# Button_ClockLed.net
KiCad netlist of a schematic drawn in Altium Designer
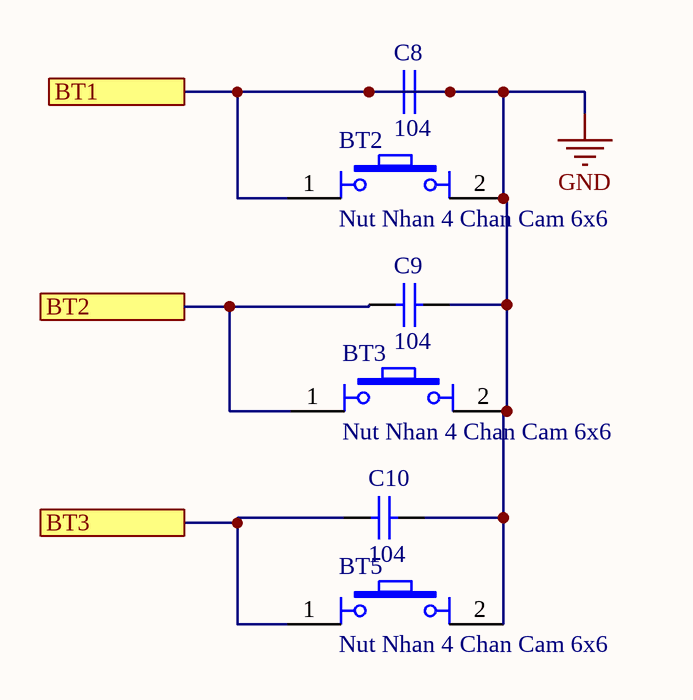
[diagram p0: Button_ClockLed.SchDoc]

(export (version "E")
  (design (tool "Eeschema 10.0.6"))
  (components
    (comp (ref "BT2")
      (value "Nut Nhan 4 Chan Cam 6x6")
      (footprint "Nut Nhan 4 Chan Cam 6x6")
      (description "Nut Nhan 4 Chan 6x6mm")
      (libsource (lib "Altium_Lib_by_KhueNguyenCreator") (part "Nut Nhan 4 Chan Cam 6x6"))
    )
    (comp (ref "BT3")
      (value "Nut Nhan 4 Chan Cam 6x6")
      (footprint "Nut Nhan 4 Chan Cam 6x6")
      (description "Nut Nhan 4 Chan 6x6mm")
      (libsource (lib "Altium_Lib_by_KhueNguyenCreator") (part "Nut Nhan 4 Chan Cam 6x6"))
    )
    (comp (ref "BT5")
      (value "Nut Nhan 4 Chan Cam 6x6")
      (footprint "Nut Nhan 4 Chan Cam 6x6")
      (description "Nut Nhan 4 Chan 6x6mm")
      (libsource (lib "Altium_Lib_by_KhueNguyenCreator") (part "Nut Nhan 4 Chan Cam 6x6"))
    )
    (comp (ref "C8")
      (value "104")
      (footprint "tu 0805")
      (description "Dán")
      (libsource (lib "Altium_Lib_by_KhueNguyenCreator") (part "Tu 0805 104 50V 10%"))
    )
    (comp (ref "C9")
      (value "104")
      (footprint "tu 0805")
      (description "Dán")
      (libsource (lib "Altium_Lib_by_KhueNguyenCreator") (part "Tu 0805 104 50V 10%"))
    )
    (comp (ref "C10")
      (value "104")
      (footprint "tu 0805")
      (description "Dán")
      (libsource (lib "Altium_Lib_by_KhueNguyenCreator") (part "Tu 0805 104 50V 10%"))
    )
  )
  (nets
    (net (code "1") (name "/BT2") (class "Default")
      (node (ref "BT3") (pin "1") (pintype "passive"))
      (node (ref "C9") (pin "1") (pinfunction "1_1") (pintype "passive"))
    )
    (net (code "2") (name "/BT3") (class "Default")
      (node (ref "BT5") (pin "1") (pintype "passive"))
      (node (ref "C10") (pin "2") (pinfunction "2_2") (pintype "passive"))
    )
    (net (code "3") (name "GND") (class "Default")
      (node (ref "BT2") (pin "1") (pintype "passive"))
      (node (ref "BT2") (pin "2") (pintype "passive"))
      (node (ref "BT3") (pin "2") (pintype "passive"))
      (node (ref "BT5") (pin "2") (pintype "passive"))
      (node (ref "C10") (pin "1") (pinfunction "1_1") (pintype "passive"))
      (node (ref "C8") (pin "1") (pinfunction "1_1") (pintype "passive"))
      (node (ref "C8") (pin "2") (pinfunction "2_2") (pintype "passive"))
      (node (ref "C9") (pin "2") (pinfunction "2_2") (pintype "passive"))
    )
  )
)
